# uc4h_gpsmagbaro_v0301.net
KiCad netlist of a schematic drawn in EAGLE
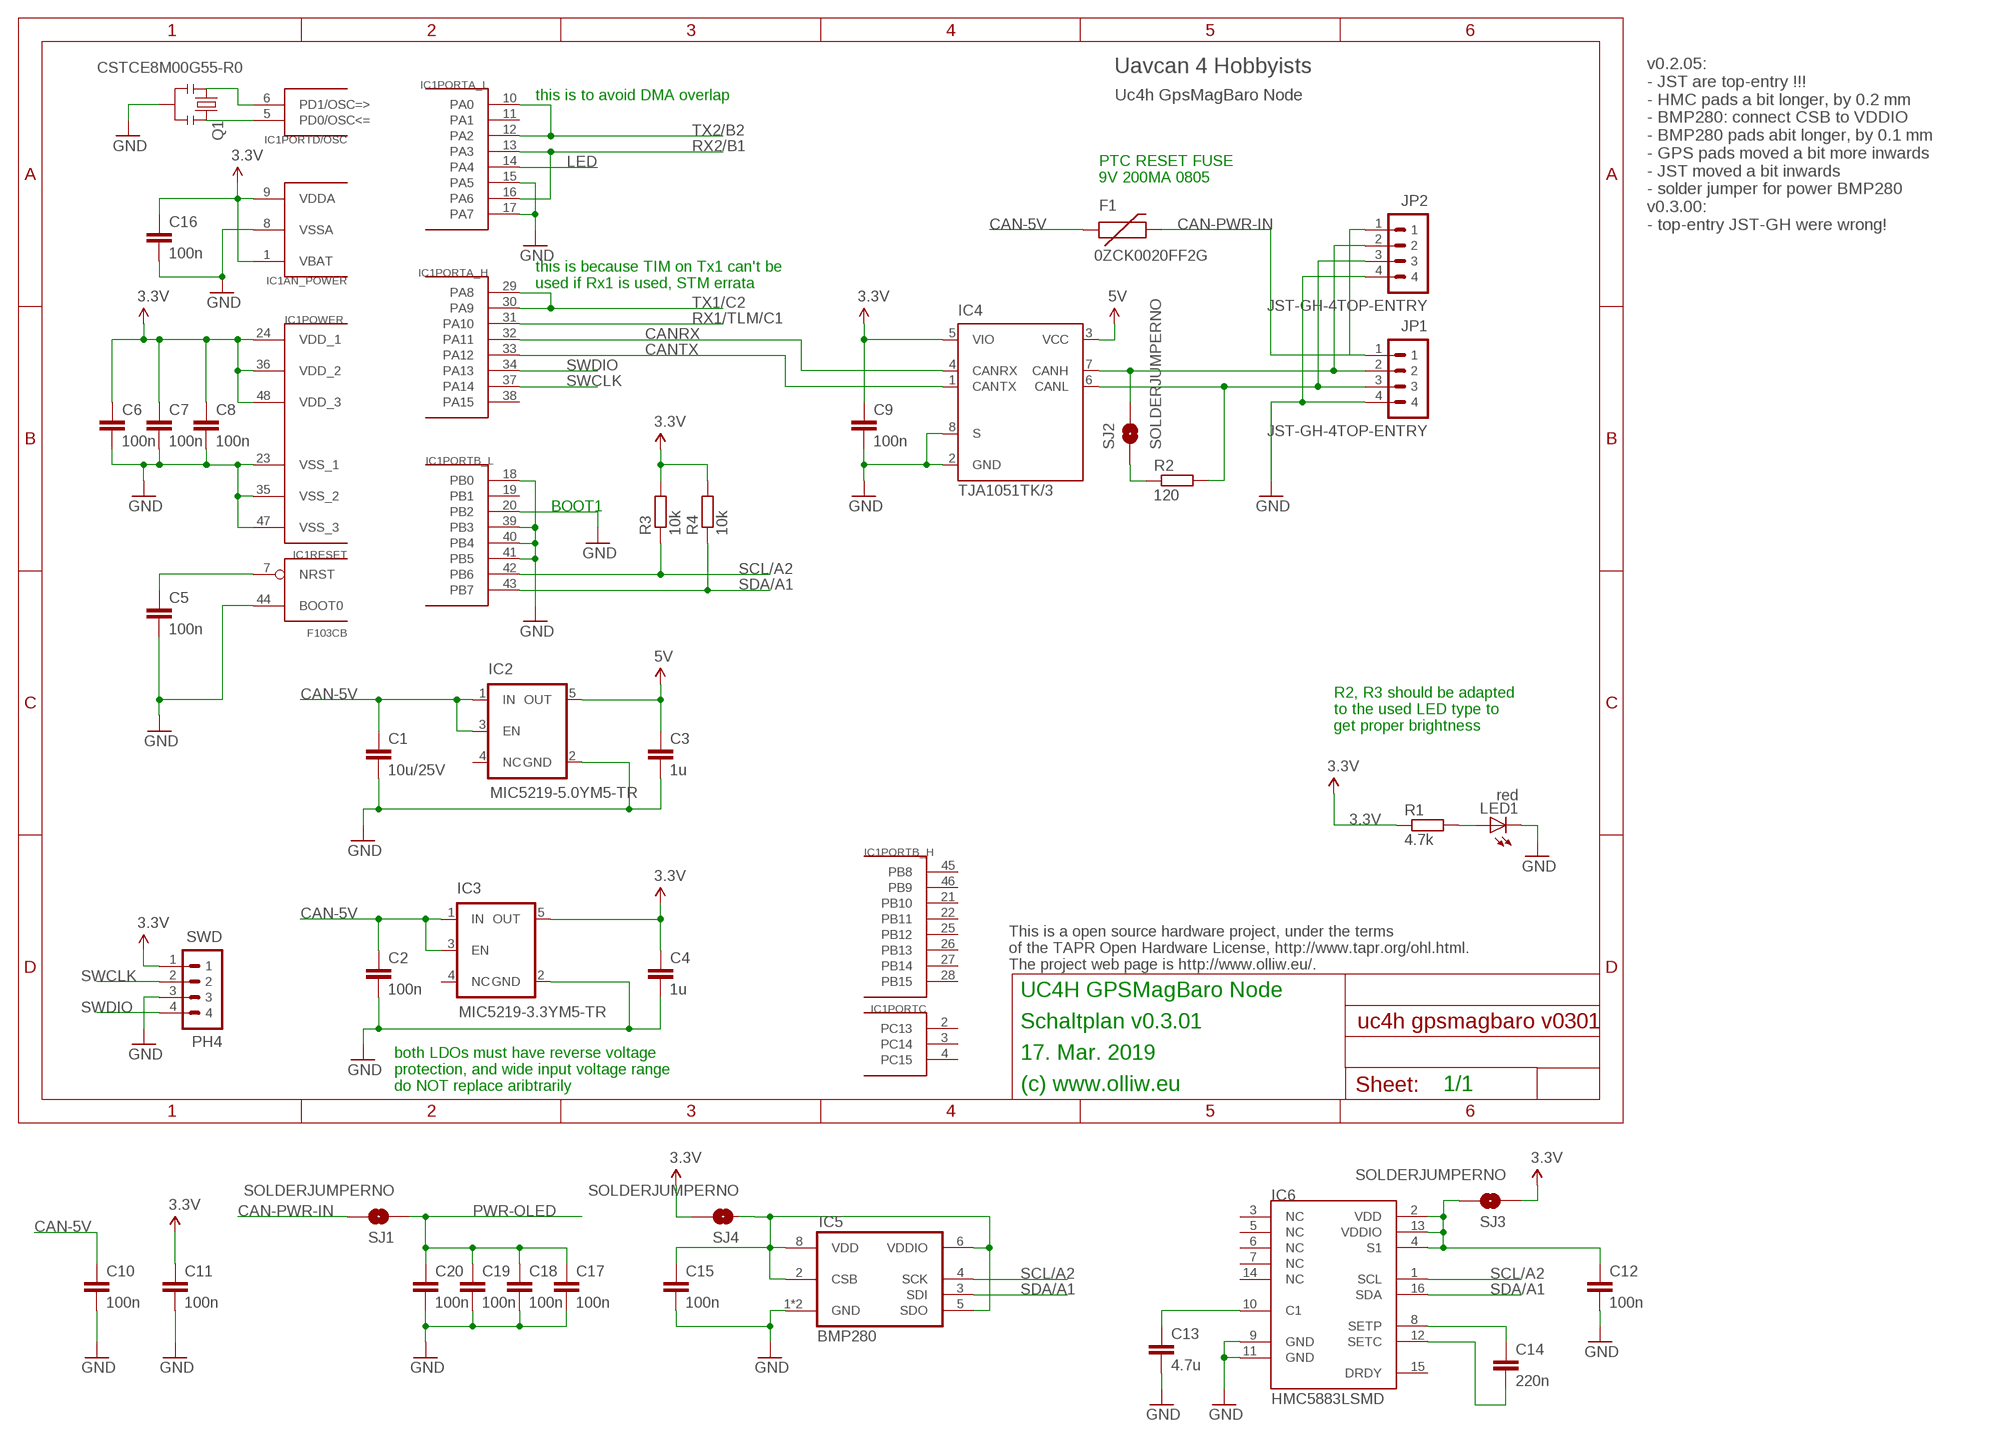
[diagram p0: schematic, sheet 1]

(export (version "E")
  (design (tool "Eeschema 10.0.6"))
  (components
    (comp (ref "C1")
      (value "10u/25V")
      (footprint "eagle-import:C1206")
      (libsource (lib "eagle-import") (part "C-EUC1206"))
    )
    (comp (ref "C2")
      (value "100n")
      (footprint "eagle-import:C0603K")
      (libsource (lib "eagle-import") (part "C-EUC0603K"))
    )
    (comp (ref "C3")
      (value "1u")
      (footprint "eagle-import:C0603K")
      (libsource (lib "eagle-import") (part "C-EUC0603K"))
    )
    (comp (ref "C4")
      (value "1u")
      (footprint "eagle-import:C0603K")
      (libsource (lib "eagle-import") (part "C-EUC0603K"))
    )
    (comp (ref "C5")
      (value "100n")
      (footprint "eagle-import:C0603K")
      (libsource (lib "eagle-import") (part "C-EUC0603K"))
    )
    (comp (ref "C6")
      (value "100n")
      (footprint "eagle-import:C0603K")
      (libsource (lib "eagle-import") (part "C-EUC0603K"))
    )
    (comp (ref "C7")
      (value "100n")
      (footprint "eagle-import:C0603K")
      (libsource (lib "eagle-import") (part "C-EUC0603K"))
    )
    (comp (ref "C8")
      (value "100n")
      (footprint "eagle-import:C0603K")
      (libsource (lib "eagle-import") (part "C-EUC0603K"))
    )
    (comp (ref "C9")
      (value "100n")
      (footprint "eagle-import:C0603K")
      (libsource (lib "eagle-import") (part "C-EUC0603K"))
    )
    (comp (ref "C10")
      (value "100n")
      (footprint "eagle-import:C0603")
      (libsource (lib "eagle-import") (part "C-EUC0603"))
    )
    (comp (ref "C11")
      (value "100n")
      (footprint "eagle-import:C0603")
      (libsource (lib "eagle-import") (part "C-EUC0603"))
    )
    (comp (ref "C12")
      (value "100n")
      (footprint "eagle-import:C0603")
      (libsource (lib "eagle-import") (part "C-EUC0603"))
    )
    (comp (ref "C13")
      (value "4.7u")
      (footprint "eagle-import:C0805")
      (libsource (lib "eagle-import") (part "C-EUC0805"))
    )
    (comp (ref "C14")
      (value "220n")
      (footprint "eagle-import:C0603")
      (libsource (lib "eagle-import") (part "C-EUC0603"))
    )
    (comp (ref "C15")
      (value "100n")
      (footprint "eagle-import:C0603")
      (libsource (lib "eagle-import") (part "C-EUC0603"))
    )
    (comp (ref "C16")
      (value "100n")
      (footprint "eagle-import:C0603")
      (libsource (lib "eagle-import") (part "C-EUC0603"))
    )
    (comp (ref "C17")
      (value "100n")
      (footprint "eagle-import:C0603")
      (libsource (lib "eagle-import") (part "C-EUC0603"))
    )
    (comp (ref "C18")
      (value "100n")
      (footprint "eagle-import:C0603")
      (libsource (lib "eagle-import") (part "C-EUC0603"))
    )
    (comp (ref "C19")
      (value "100n")
      (footprint "eagle-import:C0603")
      (libsource (lib "eagle-import") (part "C-EUC0603"))
    )
    (comp (ref "C20")
      (value "100n")
      (footprint "eagle-import:C0603")
      (libsource (lib "eagle-import") (part "C-EUC0603"))
    )
    (comp (ref "F1")
      (value "0ZCK0020FF2G")
      (footprint "eagle-import:FUSE-0805")
      (libsource (lib "eagle-import") (part "FUSE-PTCFUSE-0805"))
    )
    (comp (ref "IC1")
      (value "F103CB")
      (footprint "eagle-import:TQFP48")
      (libsource (lib "eagle-import") (part "STM32F10XCXT6"))
    )
    (comp (ref "IC2")
      (value "MIC5219-5.0YM5-TR")
      (footprint "eagle-import:SOT23-5")
      (libsource (lib "eagle-import") (part "V_REG_TPS76433SOT23-5"))
    )
    (comp (ref "IC3")
      (value "MIC5219-3.3YM5-TR")
      (footprint "eagle-import:SOT23-5")
      (libsource (lib "eagle-import") (part "V_REG_TPS76433SOT23-5"))
    )
    (comp (ref "IC4")
      (value "TJA1051TK/3")
      (footprint "eagle-import:HVSON8")
      (libsource (lib "eagle-import") (part "TJA1051TK/3"))
    )
    (comp (ref "IC5")
      (value "BMP280")
      (footprint "eagle-import:BMP280")
      (libsource (lib "eagle-import") (part "BMP280"))
    )
    (comp (ref "IC6")
      (value "HMC5883LSMD")
      (footprint "eagle-import:16LPCC")
      (libsource (lib "eagle-import") (part "HMC5883LSMD"))
    )
    (comp (ref "JP1")
      (value "JST-GH-4TOP-ENTRY")
      (footprint "eagle-import:BM04B-GHS-TBT")
      (libsource (lib "eagle-import") (part "JST-GH-4TOP-ENTRY"))
    )
    (comp (ref "JP2")
      (value "JST-GH-4TOP-ENTRY")
      (footprint "eagle-import:BM04B-GHS-TBT")
      (libsource (lib "eagle-import") (part "JST-GH-4TOP-ENTRY"))
    )
    (comp (ref "LED1")
      (value "red")
      (footprint "eagle-import:CHIPLED_0603")
      (libsource (lib "eagle-import") (part "LEDCHIPLED_0603"))
    )
    (comp (ref "Q1")
      (value "CSTCE8M00G55-R0")
      (footprint "eagle-import:RESONATOR-SMD")
      (libsource (lib "eagle-import") (part "RESONATORSMD"))
    )
    (comp (ref "R1")
      (value "4.7k")
      (footprint "eagle-import:R0603")
      (libsource (lib "eagle-import") (part "R-EU_R0603"))
    )
    (comp (ref "R2")
      (value "120")
      (footprint "eagle-import:R0603")
      (libsource (lib "eagle-import") (part "R-EU_R0603"))
    )
    (comp (ref "R3")
      (value "10k")
      (footprint "eagle-import:R0603")
      (libsource (lib "eagle-import") (part "R-EU_R0603"))
    )
    (comp (ref "R4")
      (value "10k")
      (footprint "eagle-import:R0603")
      (libsource (lib "eagle-import") (part "R-EU_R0603"))
    )
    (comp (ref "SJ1")
      (value "SOLDERJUMPERNO")
      (footprint "eagle-import:SJ_2S-NO")
      (libsource (lib "eagle-import") (part "SOLDERJUMPERNO"))
    )
    (comp (ref "SJ2")
      (value "SOLDERJUMPERNO")
      (footprint "eagle-import:SJ_2S-NO")
      (libsource (lib "eagle-import") (part "SOLDERJUMPERNO"))
    )
    (comp (ref "SJ3")
      (value "SOLDERJUMPERNO")
      (footprint "eagle-import:SJ_2S-NO")
      (libsource (lib "eagle-import") (part "SOLDERJUMPERNO"))
    )
    (comp (ref "SJ4")
      (value "SOLDERJUMPERNO")
      (footprint "eagle-import:SJ_2S-NO")
      (libsource (lib "eagle-import") (part "SOLDERJUMPERNO"))
    )
    (comp (ref "SWD")
      (value "PH4")
      (footprint "eagle-import:4X1_1P27_OCT_BILEX")
      (libsource (lib "eagle-import") (part "P4X1_1P27-OCT_BILEX"))
    )
  )
  (nets
    (net (code "1") (name "/CAN-5V") (class "Default")
      (node (ref "C1") (pin "1") (pinfunction "1_1") (pintype "passive"))
      (node (ref "C10") (pin "1") (pinfunction "1_1") (pintype "passive"))
      (node (ref "C2") (pin "1") (pinfunction "1_1") (pintype "passive"))
      (node (ref "F1") (pin "1") (pinfunction "1_1") (pintype "bidirectional"))
      (node (ref "IC2") (pin "1") (pinfunction "IN_1") (pintype "power_in"))
      (node (ref "IC2") (pin "3") (pinfunction "EN_3") (pintype "input"))
      (node (ref "IC3") (pin "1") (pinfunction "IN_1") (pintype "power_in"))
      (node (ref "IC3") (pin "3") (pinfunction "EN_3") (pintype "input"))
    )
    (net (code "2") (name "/CAN-PWR-IN") (class "Default")
      (node (ref "F1") (pin "2") (pinfunction "2_2") (pintype "bidirectional"))
      (node (ref "JP1") (pin "1") (pinfunction "1_1") (pintype "passive"))
      (node (ref "JP2") (pin "1") (pinfunction "1_1") (pintype "passive"))
      (node (ref "SJ1") (pin "2") (pinfunction "2_2") (pintype "passive"))
    )
    (net (code "3") (name "/CANRX") (class "Default")
      (node (ref "IC1") (pin "32") (pinfunction "PA11_32") (pintype "bidirectional"))
      (node (ref "IC4") (pin "4") (pinfunction "CANRX_4") (pintype "output"))
    )
    (net (code "4") (name "/CANTX") (class "Default")
      (node (ref "IC1") (pin "33") (pinfunction "PA12_33") (pintype "bidirectional"))
      (node (ref "IC4") (pin "1") (pinfunction "CANTX_1") (pintype "input"))
    )
    (net (code "5") (name "/LED") (class "Default")
      (node (ref "IC1") (pin "14") (pinfunction "PA4_14") (pintype "bidirectional"))
    )
    (net (code "6") (name "/PWR-OLED") (class "Default")
      (node (ref "C17") (pin "1") (pinfunction "1_1") (pintype "passive"))
      (node (ref "C18") (pin "1") (pinfunction "1_1") (pintype "passive"))
      (node (ref "C19") (pin "1") (pinfunction "1_1") (pintype "passive"))
      (node (ref "C20") (pin "1") (pinfunction "1_1") (pintype "passive"))
      (node (ref "SJ1") (pin "1") (pinfunction "1_1") (pintype "passive"))
    )
    (net (code "7") (name "/RX1{slash}TLM{slash}C1") (class "Default")
      (node (ref "IC1") (pin "31") (pinfunction "PA10_31") (pintype "bidirectional"))
    )
    (net (code "8") (name "/RX2{slash}B1") (class "Default")
      (node (ref "IC1") (pin "13") (pinfunction "PA3_13") (pintype "bidirectional"))
      (node (ref "IC1") (pin "16") (pinfunction "PA6_16") (pintype "bidirectional"))
    )
    (net (code "9") (name "/SCL{slash}A2") (class "Default")
      (node (ref "IC1") (pin "42") (pinfunction "PB6_42") (pintype "bidirectional"))
      (node (ref "IC5") (pin "4") (pinfunction "SCK_4") (pintype "bidirectional"))
      (node (ref "IC6") (pin "1") (pinfunction "SCL_1") (pintype "bidirectional"))
      (node (ref "R3") (pin "1") (pinfunction "1_1") (pintype "passive"))
    )
    (net (code "10") (name "/SDA{slash}A1") (class "Default")
      (node (ref "IC1") (pin "43") (pinfunction "PB7_43") (pintype "bidirectional"))
      (node (ref "IC5") (pin "3") (pinfunction "SDI_3") (pintype "bidirectional"))
      (node (ref "IC6") (pin "16") (pinfunction "SDA_16") (pintype "bidirectional"))
      (node (ref "R4") (pin "1") (pinfunction "1_1") (pintype "passive"))
    )
    (net (code "11") (name "/SWCLK") (class "Default")
      (node (ref "IC1") (pin "37") (pinfunction "PA14_37") (pintype "bidirectional"))
      (node (ref "SWD") (pin "2") (pinfunction "2_2") (pintype "passive"))
    )
    (net (code "12") (name "/SWDIO") (class "Default")
      (node (ref "IC1") (pin "34") (pinfunction "PA13_34") (pintype "bidirectional"))
      (node (ref "SWD") (pin "4") (pinfunction "4_4") (pintype "passive"))
    )
    (net (code "13") (name "/TX1{slash}C2") (class "Default")
      (node (ref "IC1") (pin "29") (pinfunction "PA8_29") (pintype "bidirectional"))
      (node (ref "IC1") (pin "30") (pinfunction "PA9_30") (pintype "bidirectional"))
    )
    (net (code "14") (name "/TX2{slash}B2") (class "Default")
      (node (ref "IC1") (pin "10") (pinfunction "PA0_10") (pintype "bidirectional"))
      (node (ref "IC1") (pin "12") (pinfunction "PA2_12") (pintype "bidirectional"))
    )
    (net (code "15") (name "3.3V") (class "Default")
      (node (ref "C11") (pin "1") (pinfunction "1_1") (pintype "passive"))
      (node (ref "C16") (pin "1") (pinfunction "1_1") (pintype "passive"))
      (node (ref "C4") (pin "1") (pinfunction "1_1") (pintype "passive"))
      (node (ref "C6") (pin "1") (pinfunction "1_1") (pintype "passive"))
      (node (ref "C7") (pin "1") (pinfunction "1_1") (pintype "passive"))
      (node (ref "C8") (pin "1") (pinfunction "1_1") (pintype "passive"))
      (node (ref "C9") (pin "1") (pinfunction "1_1") (pintype "passive"))
      (node (ref "IC1") (pin "1") (pinfunction "VBAT_1") (pintype "power_in"))
      (node (ref "IC1") (pin "24") (pinfunction "VDD_1_24") (pintype "power_in"))
      (node (ref "IC1") (pin "36") (pinfunction "VDD_2_36") (pintype "power_in"))
      (node (ref "IC1") (pin "48") (pinfunction "VDD_3_48") (pintype "power_in"))
      (node (ref "IC1") (pin "9") (pinfunction "VDDA_9") (pintype "power_in"))
      (node (ref "IC3") (pin "5") (pinfunction "OUT_5") (pintype "output"))
      (node (ref "IC4") (pin "5") (pinfunction "VIO_5") (pintype "power_in"))
      (node (ref "R1") (pin "1") (pinfunction "1_1") (pintype "passive"))
      (node (ref "R3") (pin "2") (pinfunction "2_2") (pintype "passive"))
      (node (ref "R4") (pin "2") (pinfunction "2_2") (pintype "passive"))
      (node (ref "SJ3") (pin "1") (pinfunction "1_1") (pintype "passive"))
      (node (ref "SJ4") (pin "2") (pinfunction "2_2") (pintype "passive"))
      (node (ref "SWD") (pin "1") (pinfunction "1_1") (pintype "passive"))
    )
    (net (code "16") (name "5V") (class "Default")
      (node (ref "C3") (pin "1") (pinfunction "1_1") (pintype "passive"))
      (node (ref "IC2") (pin "5") (pinfunction "OUT_5") (pintype "output"))
      (node (ref "IC4") (pin "3") (pinfunction "VCC_3") (pintype "power_in"))
    )
    (net (code "17") (name "GND") (class "Default")
      (node (ref "C1") (pin "2") (pinfunction "2_2") (pintype "passive"))
      (node (ref "C10") (pin "2") (pinfunction "2_2") (pintype "passive"))
      (node (ref "C11") (pin "2") (pinfunction "2_2") (pintype "passive"))
      (node (ref "C12") (pin "2") (pinfunction "2_2") (pintype "passive"))
      (node (ref "C13") (pin "2") (pinfunction "2_2") (pintype "passive"))
      (node (ref "C15") (pin "2") (pinfunction "2_2") (pintype "passive"))
      (node (ref "C16") (pin "2") (pinfunction "2_2") (pintype "passive"))
      (node (ref "C17") (pin "2") (pinfunction "2_2") (pintype "passive"))
      (node (ref "C18") (pin "2") (pinfunction "2_2") (pintype "passive"))
      (node (ref "C19") (pin "2") (pinfunction "2_2") (pintype "passive"))
      (node (ref "C2") (pin "2") (pinfunction "2_2") (pintype "passive"))
      (node (ref "C20") (pin "2") (pinfunction "2_2") (pintype "passive"))
      (node (ref "C3") (pin "2") (pinfunction "2_2") (pintype "passive"))
      (node (ref "C4") (pin "2") (pinfunction "2_2") (pintype "passive"))
      (node (ref "C5") (pin "2") (pinfunction "2_2") (pintype "passive"))
      (node (ref "C6") (pin "2") (pinfunction "2_2") (pintype "passive"))
      (node (ref "C7") (pin "2") (pinfunction "2_2") (pintype "passive"))
      (node (ref "C8") (pin "2") (pinfunction "2_2") (pintype "passive"))
      (node (ref "C9") (pin "2") (pinfunction "2_2") (pintype "passive"))
      (node (ref "IC1") (pin "15") (pinfunction "PA5_15") (pintype "bidirectional"))
      (node (ref "IC1") (pin "17") (pinfunction "PA7_17") (pintype "bidirectional"))
      (node (ref "IC1") (pin "18") (pinfunction "PB0_18") (pintype "bidirectional"))
      (node (ref "IC1") (pin "20") (pinfunction "PB2_20") (pintype "bidirectional"))
      (node (ref "IC1") (pin "23") (pinfunction "VSS_1_23") (pintype "power_in"))
      (node (ref "IC1") (pin "35") (pinfunction "VSS_2_35") (pintype "power_in"))
      (node (ref "IC1") (pin "39") (pinfunction "PB3_39") (pintype "bidirectional"))
      (node (ref "IC1") (pin "40") (pinfunction "PB4_40") (pintype "bidirectional"))
      (node (ref "IC1") (pin "41") (pinfunction "PB5_41") (pintype "bidirectional"))
      (node (ref "IC1") (pin "44") (pinfunction "BOOT0_44") (pintype "input"))
      (node (ref "IC1") (pin "47") (pinfunction "VSS_3_47") (pintype "power_in"))
      (node (ref "IC1") (pin "8") (pinfunction "VSSA_8") (pintype "power_in"))
      (node (ref "IC2") (pin "2") (pinfunction "GND_2") (pintype "power_in"))
      (node (ref "IC3") (pin "2") (pinfunction "GND_2") (pintype "power_in"))
      (node (ref "IC4") (pin "2") (pinfunction "GND_2") (pintype "power_in"))
      (node (ref "IC4") (pin "8") (pinfunction "S_8") (pintype "input"))
      (node (ref "IC5") (pin "1") (pinfunction "GND_1") (pintype "power_in"))
      (node (ref "IC5") (pin "7") (pinfunction "GND_7") (pintype "power_in"))
      (node (ref "IC6") (pin "11") (pinfunction "GND_11") (pintype "bidirectional"))
      (node (ref "IC6") (pin "9") (pinfunction "GND_9") (pintype "bidirectional"))
      (node (ref "JP1") (pin "4") (pinfunction "4_4") (pintype "passive"))
      (node (ref "JP2") (pin "4") (pinfunction "4_4") (pintype "passive"))
      (node (ref "LED1") (pin "C") (pinfunction "C_C") (pintype "passive"))
      (node (ref "Q1") (pin "2") (pinfunction "2_2") (pintype "passive"))
      (node (ref "SWD") (pin "3") (pinfunction "3_3") (pintype "passive"))
    )
    (net (code "18") (name "Net-(IC1G-PD0{slash}OSC<=)") (class "Default")
      (node (ref "IC1") (pin "5") (pinfunction "PD0/OSC<=_5") (pintype "bidirectional"))
      (node (ref "Q1") (pin "3") (pinfunction "3_3") (pintype "passive"))
    )
    (net (code "19") (name "Net-(IC1G-PD1{slash}OSC=>)") (class "Default")
      (node (ref "IC1") (pin "6") (pinfunction "PD1/OSC=>_6") (pintype "bidirectional"))
      (node (ref "Q1") (pin "1") (pinfunction "1_1") (pintype "passive"))
    )
    (net (code "20") (name "Net-(IC1I-NRST)") (class "Default")
      (node (ref "C5") (pin "1") (pinfunction "1_1") (pintype "passive"))
      (node (ref "IC1") (pin "7") (pinfunction "NRST_7") (pintype "input"))
    )
    (net (code "21") (name "Net-(IC4-CANH)") (class "Default")
      (node (ref "IC4") (pin "7") (pinfunction "CANH_7") (pintype "bidirectional"))
      (node (ref "JP1") (pin "2") (pinfunction "2_2") (pintype "passive"))
      (node (ref "JP2") (pin "2") (pinfunction "2_2") (pintype "passive"))
      (node (ref "SJ2") (pin "2") (pinfunction "2_2") (pintype "passive"))
    )
    (net (code "22") (name "Net-(IC4-CANL)") (class "Default")
      (node (ref "IC4") (pin "6") (pinfunction "CANL_6") (pintype "bidirectional"))
      (node (ref "JP1") (pin "3") (pinfunction "3_3") (pintype "passive"))
      (node (ref "JP2") (pin "3") (pinfunction "3_3") (pintype "passive"))
      (node (ref "R2") (pin "2") (pinfunction "2_2") (pintype "passive"))
    )
    (net (code "23") (name "Net-(IC5-CSB)") (class "Default")
      (node (ref "C15") (pin "1") (pinfunction "1_1") (pintype "passive"))
      (node (ref "IC5") (pin "2") (pinfunction "CSB_2") (pintype "input"))
      (node (ref "IC5") (pin "5") (pinfunction "SDO_5") (pintype "input"))
      (node (ref "IC5") (pin "6") (pinfunction "VDDIO_6") (pintype "power_in"))
      (node (ref "IC5") (pin "8") (pinfunction "VDD_8") (pintype "power_in"))
      (node (ref "SJ4") (pin "1") (pinfunction "1_1") (pintype "passive"))
    )
    (net (code "24") (name "Net-(IC6-C1)") (class "Default")
      (node (ref "C13") (pin "1") (pinfunction "1_1") (pintype "passive"))
      (node (ref "IC6") (pin "10") (pinfunction "C1_10") (pintype "bidirectional"))
    )
    (net (code "25") (name "Net-(IC6-S1)") (class "Default")
      (node (ref "C12") (pin "1") (pinfunction "1_1") (pintype "passive"))
      (node (ref "IC6") (pin "13") (pinfunction "VDDIO_13") (pintype "bidirectional"))
      (node (ref "IC6") (pin "2") (pinfunction "VDD_2") (pintype "bidirectional"))
      (node (ref "IC6") (pin "4") (pinfunction "S1_4") (pintype "bidirectional"))
      (node (ref "SJ3") (pin "2") (pinfunction "2_2") (pintype "passive"))
    )
    (net (code "26") (name "Net-(IC6-SETC)") (class "Default")
      (node (ref "C14") (pin "2") (pinfunction "2_2") (pintype "passive"))
      (node (ref "IC6") (pin "12") (pinfunction "SETC_12") (pintype "bidirectional"))
    )
    (net (code "27") (name "Net-(IC6-SETP)") (class "Default")
      (node (ref "C14") (pin "1") (pinfunction "1_1") (pintype "passive"))
      (node (ref "IC6") (pin "8") (pinfunction "SETP_8") (pintype "bidirectional"))
    )
    (net (code "28") (name "Net-(LED1-PadA)") (class "Default")
      (node (ref "LED1") (pin "A") (pinfunction "A_A") (pintype "passive"))
      (node (ref "R1") (pin "2") (pinfunction "2_2") (pintype "passive"))
    )
    (net (code "29") (name "Net-(R2-Pad1)") (class "Default")
      (node (ref "R2") (pin "1") (pinfunction "1_1") (pintype "passive"))
      (node (ref "SJ2") (pin "1") (pinfunction "1_1") (pintype "passive"))
    )
    (net (code "30") (name "unconnected-(IC1B-PA15-Pad38)") (class "Default")
      (node (ref "IC1") (pin "38") (pinfunction "PA15_38") (pintype "bidirectional"))
    )
    (net (code "31") (name "unconnected-(IC1C-PA1-Pad11)") (class "Default")
      (node (ref "IC1") (pin "11") (pinfunction "PA1_11") (pintype "bidirectional"))
    )
    (net (code "32") (name "unconnected-(IC1D-PB8-Pad45)") (class "Default")
      (node (ref "IC1") (pin "45") (pinfunction "PB8_45") (pintype "bidirectional"))
    )
    (net (code "33") (name "unconnected-(IC1D-PB9-Pad46)") (class "Default")
      (node (ref "IC1") (pin "46") (pinfunction "PB9_46") (pintype "bidirectional"))
    )
    (net (code "34") (name "unconnected-(IC1D-PB10-Pad21)") (class "Default")
      (node (ref "IC1") (pin "21") (pinfunction "PB10_21") (pintype "bidirectional"))
    )
    (net (code "35") (name "unconnected-(IC1D-PB11-Pad22)") (class "Default")
      (node (ref "IC1") (pin "22") (pinfunction "PB11_22") (pintype "bidirectional"))
    )
    (net (code "36") (name "unconnected-(IC1D-PB12-Pad25)") (class "Default")
      (node (ref "IC1") (pin "25") (pinfunction "PB12_25") (pintype "bidirectional"))
    )
    (net (code "37") (name "unconnected-(IC1D-PB13-Pad26)") (class "Default")
      (node (ref "IC1") (pin "26") (pinfunction "PB13_26") (pintype "bidirectional"))
    )
    (net (code "38") (name "unconnected-(IC1D-PB14-Pad27)") (class "Default")
      (node (ref "IC1") (pin "27") (pinfunction "PB14_27") (pintype "bidirectional"))
    )
    (net (code "39") (name "unconnected-(IC1D-PB15-Pad28)") (class "Default")
      (node (ref "IC1") (pin "28") (pinfunction "PB15_28") (pintype "bidirectional"))
    )
    (net (code "40") (name "unconnected-(IC1E-PB1-Pad19)") (class "Default")
      (node (ref "IC1") (pin "19") (pinfunction "PB1_19") (pintype "bidirectional"))
    )
    (net (code "41") (name "unconnected-(IC1F-PC13-Pad2)") (class "Default")
      (node (ref "IC1") (pin "2") (pinfunction "PC13_2") (pintype "bidirectional"))
    )
    (net (code "42") (name "unconnected-(IC1F-PC14-Pad3)") (class "Default")
      (node (ref "IC1") (pin "3") (pinfunction "PC14_3") (pintype "bidirectional"))
    )
    (net (code "43") (name "unconnected-(IC1F-PC15-Pad4)") (class "Default")
      (node (ref "IC1") (pin "4") (pinfunction "PC15_4") (pintype "bidirectional"))
    )
    (net (code "44") (name "unconnected-(IC2-NC-Pad4)") (class "Default")
      (node (ref "IC2") (pin "4") (pinfunction "NC_4") (pintype "passive"))
    )
    (net (code "45") (name "unconnected-(IC3-NC-Pad4)") (class "Default")
      (node (ref "IC3") (pin "4") (pinfunction "NC_4") (pintype "passive"))
    )
    (net (code "46") (name "unconnected-(IC6-DRDY-Pad15)") (class "Default")
      (node (ref "IC6") (pin "15") (pinfunction "DRDY_15") (pintype "bidirectional"))
    )
    (net (code "47") (name "unconnected-(IC6-NC-Pad3)") (class "Default")
      (node (ref "IC6") (pin "3") (pinfunction "NC_3") (pintype "bidirectional"))
    )
    (net (code "48") (name "unconnected-(IC6-NC-Pad5)") (class "Default")
      (node (ref "IC6") (pin "5") (pinfunction "NC_5") (pintype "bidirectional"))
    )
    (net (code "49") (name "unconnected-(IC6-NC-Pad6)") (class "Default")
      (node (ref "IC6") (pin "6") (pinfunction "NC_6") (pintype "bidirectional"))
    )
    (net (code "50") (name "unconnected-(IC6-NC-Pad7)") (class "Default")
      (node (ref "IC6") (pin "7") (pinfunction "NC_7") (pintype "bidirectional"))
    )
    (net (code "51") (name "unconnected-(IC6-NC-Pad14)") (class "Default")
      (node (ref "IC6") (pin "14") (pinfunction "NC_14") (pintype "bidirectional"))
    )
  )
)
